# AST1036.net
KiCad netlist of a schematic drawn in EAGLE
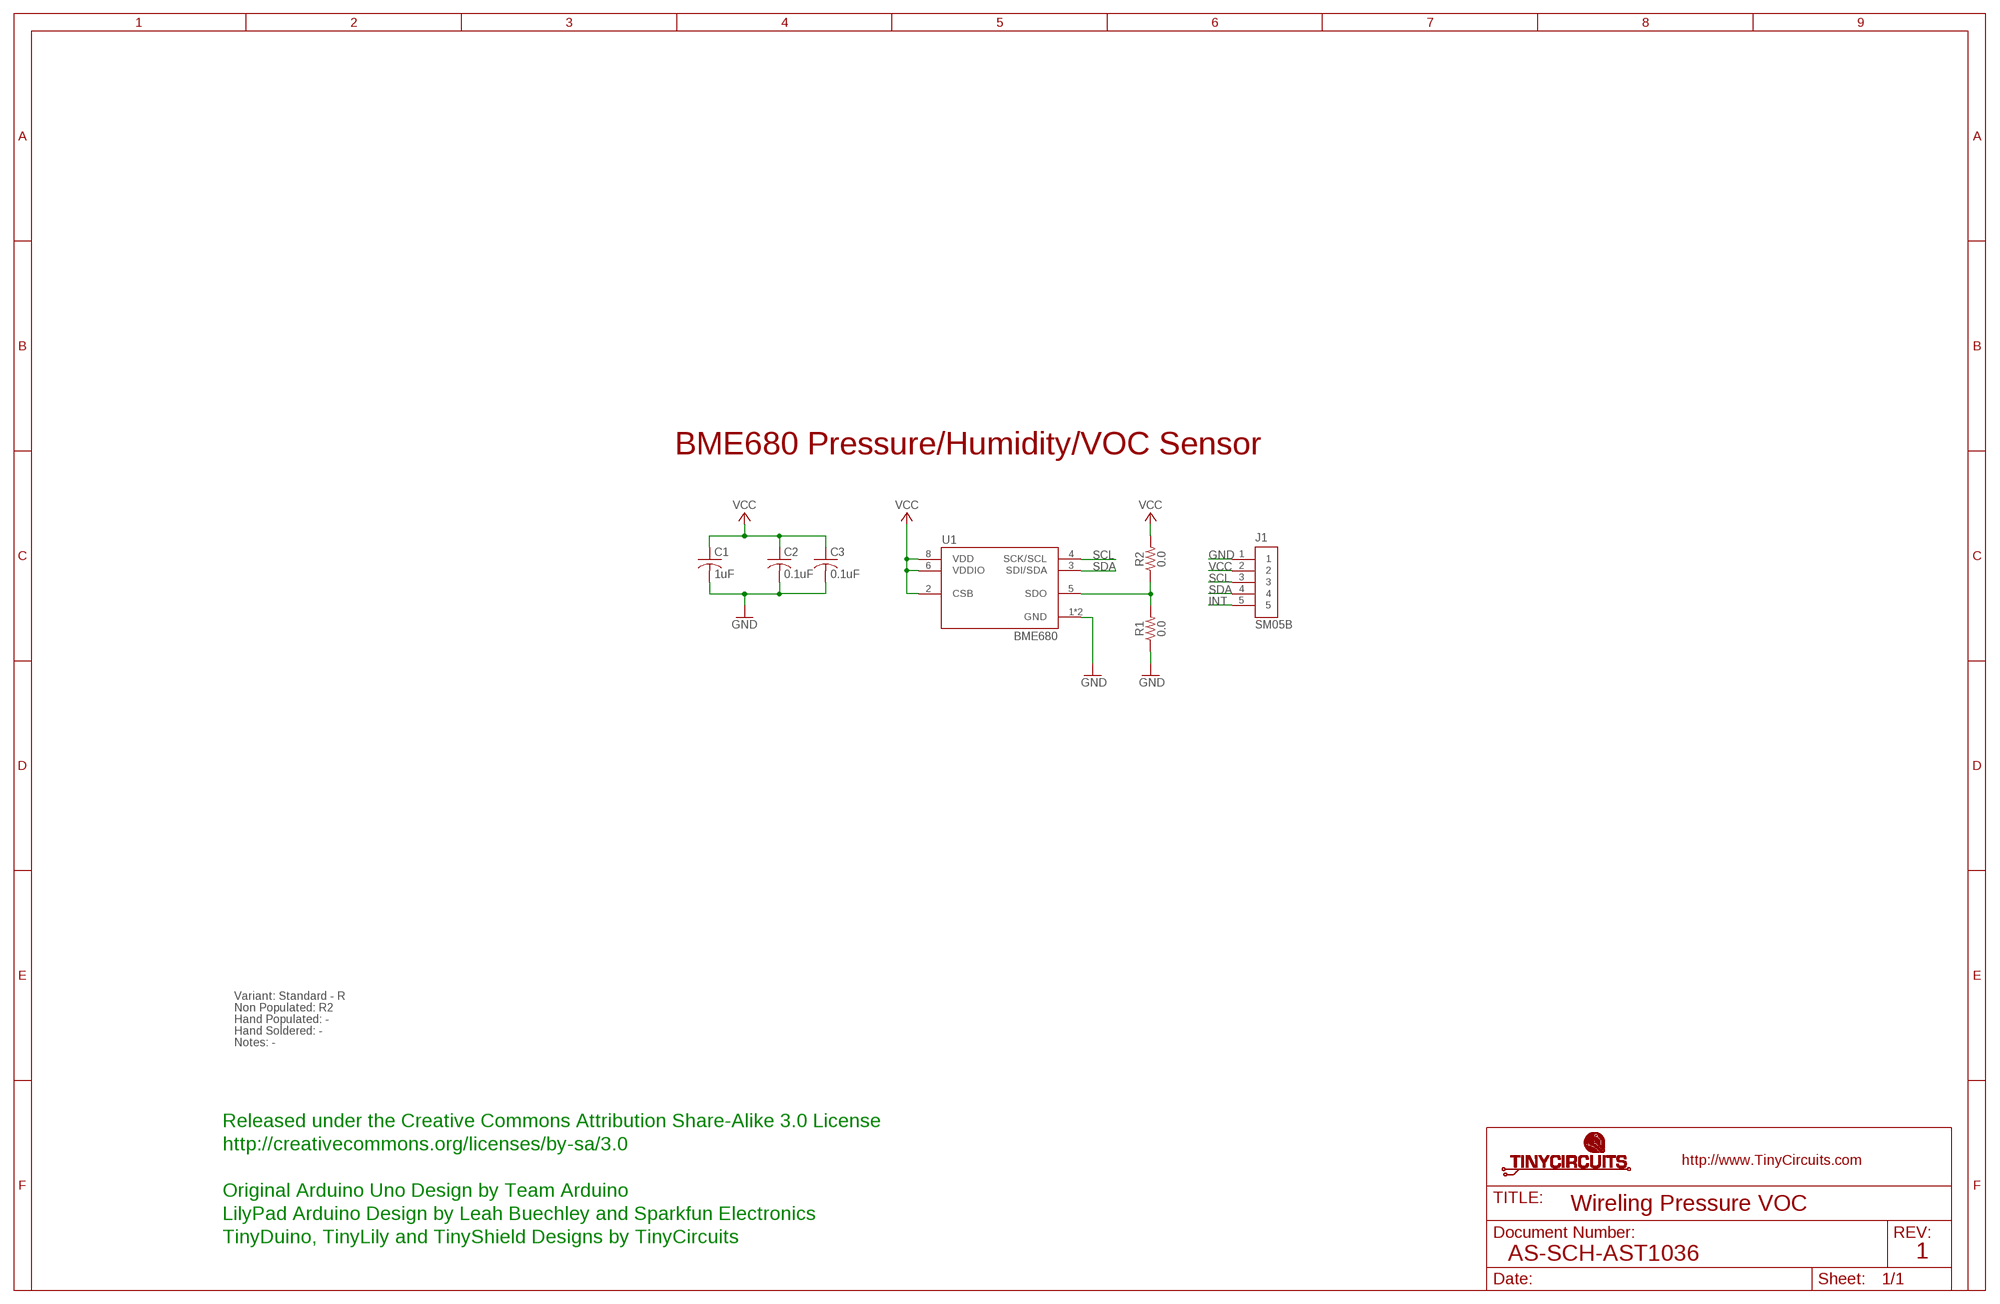
[diagram p0: schematic, sheet 1]

(export (version "E")
  (design (tool "Eeschema 10.0.6"))
  (components
    (comp (ref "C1")
      (value "1uF")
      (footprint "eagle-import:C0603")
      (fields (field (name "PARTNO") "AS-ITM-00410") (field (name "PARTNO_1") "AS-ITM-00410"))
      (libsource (lib "eagle-import") (part "AS-ITM-00410"))
    )
    (comp (ref "C2")
      (value "0.1uF")
      (footprint "eagle-import:C0402")
      (fields (field (name "PARTNO") "AS-ITM-00008"))
      (libsource (lib "eagle-import") (part "AS-ITM-00008"))
    )
    (comp (ref "C3")
      (value "0.1uF")
      (footprint "eagle-import:C0402")
      (fields (field (name "PARTNO") "AS-ITM-00008") (field (name "PARTNO_1") "AS-ITM-00008"))
      (libsource (lib "eagle-import") (part "AS-ITM-00008"))
    )
    (comp (ref "J1")
      (value "SM05B")
      (footprint "eagle-import:JST_SH_5X1_EDGE")
      (fields (field (name "PARTNO") "AS-ITM-00340"))
      (libsource (lib "eagle-import") (part "AS-ITM-00340EDGE"))
    )
    (comp (ref "R1")
      (value "0.0")
      (footprint "eagle-import:0402")
      (fields (field (name "PARTNO") "AS-ITM-00076"))
      (libsource (lib "eagle-import") (part "AS-ITM-00076"))
    )
    (comp (ref "R2")
      (value "0.0")
      (footprint "eagle-import:0402")
      (fields (field (name "PARTNO") "AS-ITM-00076") (field (name "PARTNO_1") "AS-ITM-00076"))
      (libsource (lib "eagle-import") (part "AS-ITM-00076"))
    )
    (comp (ref "U1")
      (value "BME680")
      (footprint "eagle-import:BME680")
      (fields (field (name "PARTNO") "AS-ITM-00396"))
      (libsource (lib "eagle-import") (part "AS-ITM-00396"))
    )
  )
  (nets
    (net (code "1") (name "/INT") (class "Default")
      (node (ref "J1") (pin "5") (pinfunction "5_5") (pintype "bidirectional"))
    )
    (net (code "2") (name "/SCL") (class "Default")
      (node (ref "J1") (pin "3") (pinfunction "3_3") (pintype "bidirectional"))
      (node (ref "U1") (pin "4") (pinfunction "SCK/SCL_4") (pintype "bidirectional"))
    )
    (net (code "3") (name "/SDA") (class "Default")
      (node (ref "J1") (pin "4") (pinfunction "4_4") (pintype "bidirectional"))
      (node (ref "U1") (pin "3") (pinfunction "SDI/SDA_3") (pintype "bidirectional"))
    )
    (net (code "4") (name "GND") (class "Default")
      (node (ref "C1") (pin "2") (pinfunction "2_2") (pintype "passive"))
      (node (ref "C2") (pin "2") (pinfunction "2_2") (pintype "passive"))
      (node (ref "C3") (pin "2") (pinfunction "2_2") (pintype "passive"))
      (node (ref "J1") (pin "1") (pinfunction "1_1") (pintype "bidirectional"))
      (node (ref "R1") (pin "1") (pinfunction "1_1") (pintype "passive"))
      (node (ref "U1") (pin "1") (pinfunction "GND_1") (pintype "bidirectional"))
      (node (ref "U1") (pin "7") (pinfunction "GND_7") (pintype "bidirectional"))
    )
    (net (code "5") (name "Net-(U1-SDO)") (class "Default")
      (node (ref "R1") (pin "2") (pinfunction "2_2") (pintype "passive"))
      (node (ref "R2") (pin "1") (pinfunction "1_1") (pintype "passive"))
      (node (ref "U1") (pin "5") (pinfunction "SDO_5") (pintype "bidirectional"))
    )
    (net (code "6") (name "VCC") (class "Default")
      (node (ref "C1") (pin "1") (pinfunction "1_1") (pintype "passive"))
      (node (ref "C2") (pin "1") (pinfunction "1_1") (pintype "passive"))
      (node (ref "C3") (pin "1") (pinfunction "1_1") (pintype "passive"))
      (node (ref "J1") (pin "2") (pinfunction "2_2") (pintype "bidirectional"))
      (node (ref "R2") (pin "2") (pinfunction "2_2") (pintype "passive"))
      (node (ref "U1") (pin "2") (pinfunction "CSB_2") (pintype "bidirectional"))
      (node (ref "U1") (pin "6") (pinfunction "VDDIO_6") (pintype "bidirectional"))
      (node (ref "U1") (pin "8") (pinfunction "VDD_8") (pintype "bidirectional"))
    )
  )
)
